# hrng.net
KiCad netlist of a schematic drawn in Altium Designer
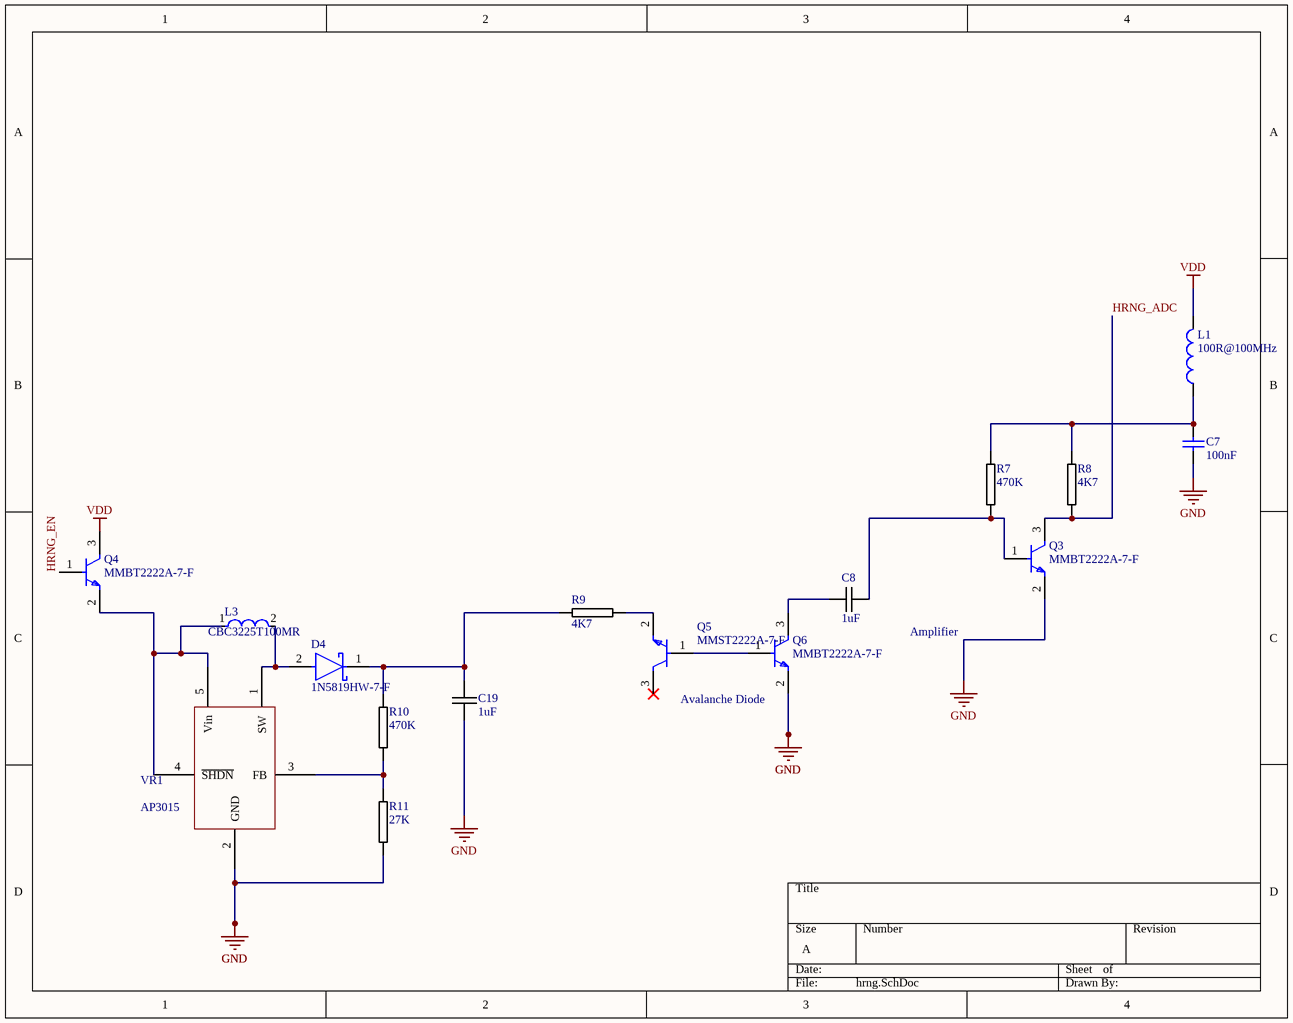
[diagram p0: hrng.SchDoc]

(export (version "E")
  (design (tool "Eeschema 10.0.6"))
  (components
    (comp (ref "C7")
      (value "100nF")
      (footprint "C0402")
      (description "Capacitor, MLCC, 100nF, 16V, X7R, 10%, 0402, T=0,5mm")
      (fields
        (field (name "INTERNAL_PART_NUMBER") "MCD-00102")
        (field (name "MANUFACTURER_PART_NUMBER") "CC0402KRX7R7BB104")
        (field (name "PROVIDED_BY") "SUBCO")
      )
      (libsource (lib "MB1272") (part "MCD-00102"))
    )
    (comp (ref "C8")
      (value "1uF")
      (footprint "0402C-GENERIC")
      (description "CAPACITOR 0402 CERAMIC")
      (libsource (lib "vh_altium_library") (part "0402C-1UF-25V-X5R-SAM"))
    )
    (comp (ref "C19")
      (value "1uF")
      (footprint "0402C-GENERIC")
      (description "CAPACITOR 0402 CERAMIC")
      (libsource (lib "vh_altium_library") (part "0402C-1UF-25V-X5R-SAM"))
    )
    (comp (ref "D4")
      (value "1N5819HW-7-F")
      (footprint "FP-SOD123-IPC_A")
      (description "DIODE SCHOTTKY 40V 1A SOD123")
      (libsource (lib "Altium Content Vault") (part "1d6ec82d83fb6aee721767c19dac4b9"))
    )
    (comp (ref "L1")
      (value "100R@100MHz")
      (footprint "FIL_0603_H0P65")
      (description "Ferrite bead 100R 2A 0603")
      (fields
        (field (name "INTERNAL_PART_NUMBER") "MCD-00094")
        (field (name "MANUFACTURER_PART_NUMBER") "BLM18EG101TN1")
        (field (name "PROVIDED_BY") "SUBCO")
      )
      (libsource (lib "MB1272") (part "MCD-00094"))
    )
    (comp (ref "L3")
      (value "CBC3225T100MR")
      (footprint "FP-CB3225-IPC_A")
      (description "SMD Inductors 10uH ±20% 0.9A 0.1729Ω 1210")
      (fields (field (name "TOLERANCE") "20%"))
      (libsource (lib "Altium Content Vault") (part "725321dda6339637d4d059423bc1c3c"))
    )
    (comp (ref "Q3")
      (value "MMBT2222A-7-F")
      (footprint "FP-SOT23-IPC_A")
      (description "TRANS NPN 40V 0.6A SMD SOT23-3")
      (fields (field (name "VOLTAGE") "40V"))
      (libsource (lib "Altium Content Vault") (part "b44e953556f554d0102664c7d152cb4"))
    )
    (comp (ref "Q4")
      (value "MMBT2222A-7-F")
      (footprint "FP-SOT23-IPC_A")
      (description "TRANS NPN 40V 0.6A SMD SOT23-3")
      (fields (field (name "VOLTAGE") "40V"))
      (libsource (lib "Altium Content Vault") (part "b44e953556f554d0102664c7d152cb4"))
    )
    (comp (ref "Q5")
      (value "MMST2222A-7-F")
      (footprint "FP-SOT23-IPC_A")
      (description "TRANS NPN 40V 0.6A SMD SOT23-3")
      (fields (field (name "VOLTAGE") "40V"))
      (libsource (lib "Altium Content Vault") (part "b44e953556f554d0102664c7d152cb4"))
    )
    (comp (ref "Q6")
      (value "MMBT2222A-7-F")
      (footprint "FP-SOT23-IPC_A")
      (description "TRANS NPN 40V 0.6A SMD SOT23-3")
      (fields (field (name "VOLTAGE") "40V"))
      (libsource (lib "Altium Content Vault") (part "b44e953556f554d0102664c7d152cb4"))
    )
    (comp (ref "R7")
      (value "470K")
      (footprint "0603R-470K")
      (description "GENERIC RESISTOR 0603")
      (fields
        (field (name "MANUFACTURER PART NUMBER") "RMCF 1/16 470K 1% R")
        (field (name "TOLERANCE") "±1%")
      )
      (libsource (lib "vh_altium_library") (part "0603R-470K"))
    )
    (comp (ref "R8")
      (value "4K7")
      (footprint "0603R-4K7")
      (description "GENERIC RESISTOR 0603")
      (fields
        (field (name "MANUFACTURER") "Stackpole Electronics Inc")
        (field (name "MANUFACTURER PART NUMBER") "RMCF 1/16 4.7K 1% R")
      )
      (libsource (lib "vh_altium_library") (part "0603R-4K7"))
    )
    (comp (ref "R9")
      (value "4K7")
      (footprint "0603R-4K7")
      (description "GENERIC RESISTOR 0603")
      (fields
        (field (name "MANUFACTURER") "Stackpole Electronics Inc")
        (field (name "MANUFACTURER PART NUMBER") "RMCF 1/16 4.7K 1% R")
      )
      (libsource (lib "vh_altium_library") (part "0603R-4K7"))
    )
    (comp (ref "R10")
      (value "470K")
      (footprint "0603R-470K")
      (description "GENERIC RESISTOR 0603")
      (fields
        (field (name "MANUFACTURER PART NUMBER") "RMCF 1/16 470K 1% R")
        (field (name "TOLERANCE") "±1%")
      )
      (libsource (lib "vh_altium_library") (part "0603R-470K"))
    )
    (comp (ref "R11")
      (value "27K")
      (footprint "0603R-27K")
      (description "GENERIC RESISTOR 0603")
      (fields (field (name "TOLERANCE") "±1%") (field (name "MANUFACTURER") "Stackpole Electronics Inc"))
      (libsource (lib "vh_altium_library") (part "0603R-27K"))
    )
    (comp (ref "VR1")
      (value "AP3015")
      (footprint "SOT23-5")
      (libsource (lib "vh_altium_library") (part "LT1930A"))
    )
  )
  (nets
    (net (code "1") (name "/HRNG_ADC") (class "Default")
      (node (ref "Q3") (pin "3") (pinfunction "C_3") (pintype "passive"))
      (node (ref "R8") (pin "1") (pintype "passive"))
    )
    (net (code "2") (name "/HRNG_EN") (class "Default")
      (node (ref "Q4") (pin "1") (pinfunction "B_1") (pintype "passive"))
    )
    (net (code "3") (name "GND") (class "Default")
      (node (ref "C19") (pin "2") (pintype "passive"))
      (node (ref "C7") (pin "1") (pinfunction "1_1") (pintype "passive"))
      (node (ref "Q3") (pin "2") (pinfunction "E_2") (pintype "passive"))
      (node (ref "Q6") (pin "2") (pinfunction "E_2") (pintype "passive"))
      (node (ref "R11") (pin "2") (pintype "passive"))
      (node (ref "VR1") (pin "2") (pinfunction "GND_2") (pintype "passive"))
    )
    (net (code "4") (name "Net-(C7-Pad2)") (class "Default")
      (node (ref "C7") (pin "2") (pinfunction "2_2") (pintype "passive"))
      (node (ref "L1") (pin "1") (pinfunction "1_1") (pintype "passive"))
      (node (ref "R7") (pin "1") (pintype "passive"))
      (node (ref "R8") (pin "2") (pintype "passive"))
    )
    (net (code "5") (name "Net-(D4-A)") (class "Default")
      (node (ref "D4") (pin "2") (pinfunction "A_2") (pintype "passive"))
      (node (ref "L3") (pin "2") (pinfunction "2_2") (pintype "passive"))
      (node (ref "VR1") (pin "1") (pinfunction "SW_1") (pintype "passive"))
    )
    (net (code "6") (name "Net-(D4-C)") (class "Default")
      (node (ref "C19") (pin "1") (pintype "passive"))
      (node (ref "D4") (pin "1") (pinfunction "C_1") (pintype "passive"))
      (node (ref "R10") (pin "1") (pintype "passive"))
      (node (ref "R9") (pin "1") (pintype "passive"))
    )
    (net (code "7") (name "Net-(Q3-B)") (class "Default")
      (node (ref "C8") (pin "2") (pintype "passive"))
      (node (ref "Q3") (pin "1") (pinfunction "B_1") (pintype "passive"))
      (node (ref "R7") (pin "2") (pintype "passive"))
    )
    (net (code "8") (name "Net-(Q4-E)") (class "Default")
      (node (ref "L3") (pin "1") (pinfunction "1_1") (pintype "passive"))
      (node (ref "Q4") (pin "2") (pinfunction "E_2") (pintype "passive"))
      (node (ref "VR1") (pin "4") (pinfunction "~{SHDN}_4") (pintype "passive"))
      (node (ref "VR1") (pin "5") (pinfunction "Vin_5") (pintype "passive"))
    )
    (net (code "9") (name "Net-(Q5-B)") (class "Default")
      (node (ref "Q5") (pin "1") (pinfunction "B_1") (pintype "passive"))
      (node (ref "Q6") (pin "1") (pinfunction "B_1") (pintype "passive"))
    )
    (net (code "10") (name "Net-(Q5-E)") (class "Default")
      (node (ref "Q5") (pin "2") (pinfunction "E_2") (pintype "passive"))
      (node (ref "R9") (pin "2") (pintype "passive"))
    )
    (net (code "11") (name "Net-(Q6-C)") (class "Default")
      (node (ref "C8") (pin "1") (pintype "passive"))
      (node (ref "Q6") (pin "3") (pinfunction "C_3") (pintype "passive"))
    )
    (net (code "12") (name "Net-(VR1-FB)") (class "Default")
      (node (ref "R10") (pin "2") (pintype "passive"))
      (node (ref "R11") (pin "1") (pintype "passive"))
      (node (ref "VR1") (pin "3") (pinfunction "FB_3") (pintype "passive"))
    )
    (net (code "13") (name "VDD") (class "Default")
      (node (ref "L1") (pin "2") (pinfunction "2_2") (pintype "passive"))
      (node (ref "Q4") (pin "3") (pinfunction "C_3") (pintype "passive"))
    )
    (net (code "14") (name "unconnected-(Q5-C-Pad3)") (class "Default")
      (node (ref "Q5") (pin "3") (pinfunction "C_3") (pintype "passive+no_connect"))
    )
  )
)
